# NTC.net
KiCad netlist of a schematic drawn in Altium Designer
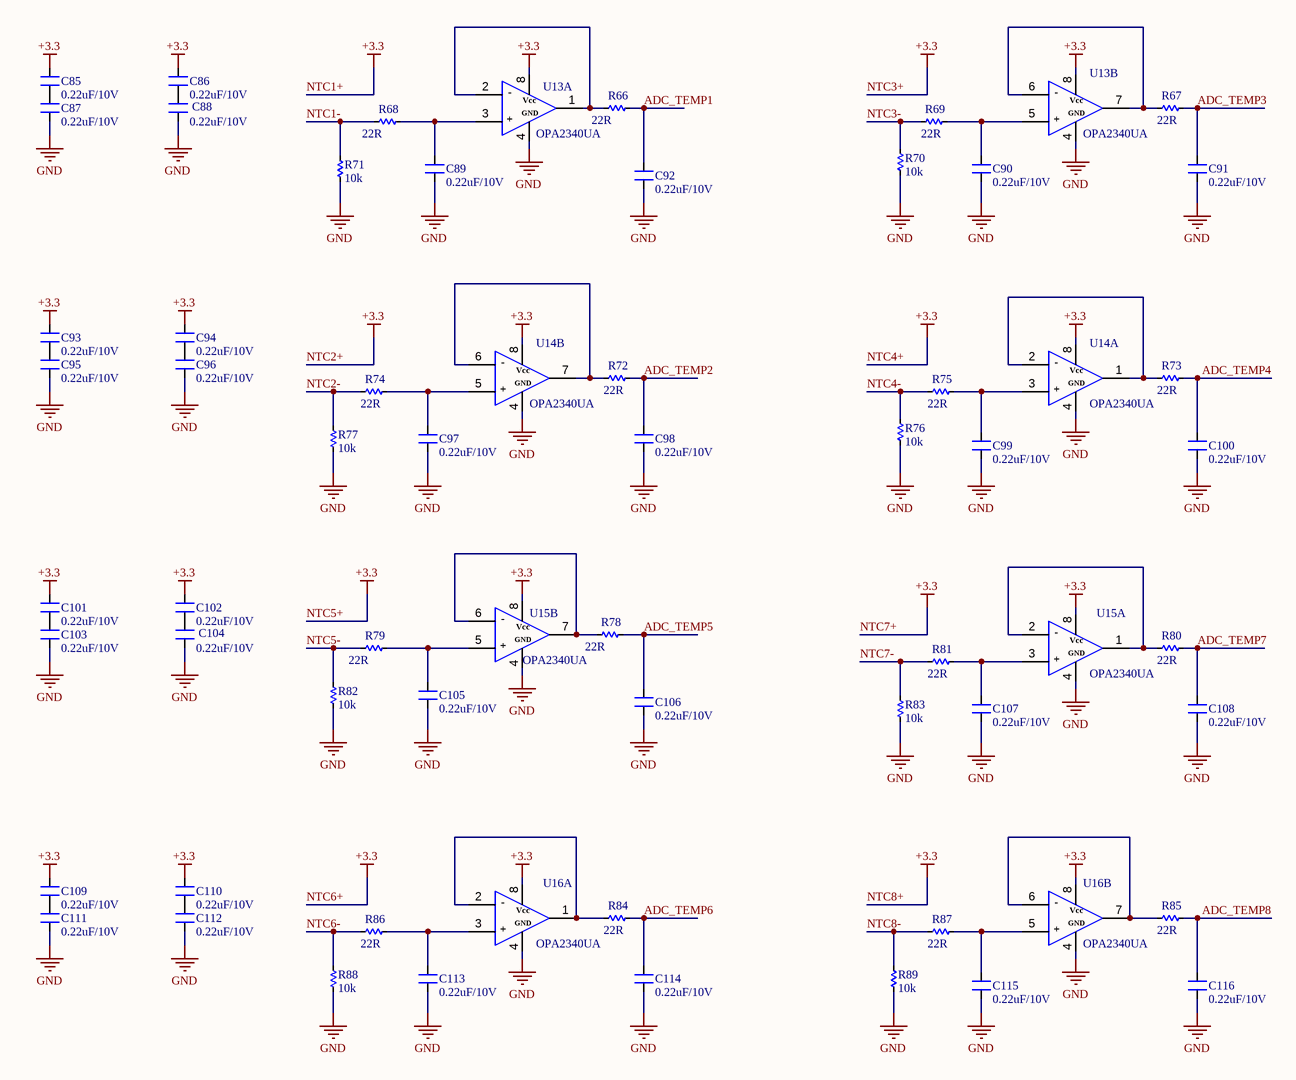
[diagram p0: NTC.SchDoc]

(export (version "E")
  (design (tool "Eeschema 10.0.6"))
  (components
    (comp (ref "C85")
      (value "0.22uF/10V")
      (footprint "CAP_C_1608X80")
      (libsource (lib "Sang_library") (part "Capacitors"))
    )
    (comp (ref "C86")
      (value "0.22uF/10V")
      (footprint "CAP_C_1608X80")
      (libsource (lib "Sang_library") (part "Capacitors"))
    )
    (comp (ref "C87")
      (value "0.22uF/10V")
      (footprint "CAP_C_1608X80")
      (libsource (lib "Sang_library") (part "Capacitors"))
    )
    (comp (ref "C88")
      (value "0.22uF/10V")
      (footprint "CAP_C_1608X80")
      (libsource (lib "Sang_library") (part "Capacitors"))
    )
    (comp (ref "C89")
      (value "0.22uF/10V")
      (footprint "CAP_C_1608X80")
      (libsource (lib "Sang_library") (part "Capacitors"))
    )
    (comp (ref "C90")
      (value "0.22uF/10V")
      (footprint "CAP_C_1608X80")
      (libsource (lib "Sang_library") (part "Capacitors"))
    )
    (comp (ref "C91")
      (value "0.22uF/10V")
      (footprint "CAP_C_1608X80")
      (libsource (lib "Sang_library") (part "Capacitors"))
    )
    (comp (ref "C92")
      (value "0.22uF/10V")
      (footprint "CAP_C_1608X80")
      (libsource (lib "Sang_library") (part "Capacitors"))
    )
    (comp (ref "C93")
      (value "0.22uF/10V")
      (footprint "CAP_C_1608X80")
      (libsource (lib "Sang_library") (part "Capacitors"))
    )
    (comp (ref "C94")
      (value "0.22uF/10V")
      (footprint "CAP_C_1608X80")
      (libsource (lib "Sang_library") (part "Capacitors"))
    )
    (comp (ref "C95")
      (value "0.22uF/10V")
      (footprint "CAP_C_1608X80")
      (libsource (lib "Sang_library") (part "Capacitors"))
    )
    (comp (ref "C96")
      (value "0.22uF/10V")
      (footprint "CAP_C_1608X80")
      (libsource (lib "Sang_library") (part "Capacitors"))
    )
    (comp (ref "C97")
      (value "0.22uF/10V")
      (footprint "CAP_C_1608X80")
      (libsource (lib "Sang_library") (part "Capacitors"))
    )
    (comp (ref "C98")
      (value "0.22uF/10V")
      (footprint "CAP_C_1608X80")
      (libsource (lib "Sang_library") (part "Capacitors"))
    )
    (comp (ref "C99")
      (value "0.22uF/10V")
      (footprint "CAP_C_1608X80")
      (libsource (lib "Sang_library") (part "Capacitors"))
    )
    (comp (ref "C100")
      (value "0.22uF/10V")
      (footprint "CAP_C_1608X80")
      (libsource (lib "Sang_library") (part "Capacitors"))
    )
    (comp (ref "C101")
      (value "0.22uF/10V")
      (footprint "CAP_C_1608X80")
      (libsource (lib "Sang_library") (part "Capacitors"))
    )
    (comp (ref "C102")
      (value "0.22uF/10V")
      (footprint "CAP_C_1608X80")
      (libsource (lib "Sang_library") (part "Capacitors"))
    )
    (comp (ref "C103")
      (value "0.22uF/10V")
      (footprint "CAP_C_1608X80")
      (libsource (lib "Sang_library") (part "Capacitors"))
    )
    (comp (ref "C104")
      (value "0.22uF/10V")
      (footprint "CAP_C_1608X80")
      (libsource (lib "Sang_library") (part "Capacitors"))
    )
    (comp (ref "C105")
      (value "0.22uF/10V")
      (footprint "CAP_C_1608X80")
      (libsource (lib "Sang_library") (part "Capacitors"))
    )
    (comp (ref "C106")
      (value "0.22uF/10V")
      (footprint "CAP_C_1608X80")
      (libsource (lib "Sang_library") (part "Capacitors"))
    )
    (comp (ref "C107")
      (value "0.22uF/10V")
      (footprint "CAP_C_1608X80")
      (libsource (lib "Sang_library") (part "Capacitors"))
    )
    (comp (ref "C108")
      (value "0.22uF/10V")
      (footprint "CAP_C_1608X80")
      (libsource (lib "Sang_library") (part "Capacitors"))
    )
    (comp (ref "C109")
      (value "0.22uF/10V")
      (footprint "CAP_C_1608X80")
      (libsource (lib "Sang_library") (part "Capacitors"))
    )
    (comp (ref "C110")
      (value "0.22uF/10V")
      (footprint "CAP_C_1608X80")
      (libsource (lib "Sang_library") (part "Capacitors"))
    )
    (comp (ref "C111")
      (value "0.22uF/10V")
      (footprint "CAP_C_1608X80")
      (libsource (lib "Sang_library") (part "Capacitors"))
    )
    (comp (ref "C112")
      (value "0.22uF/10V")
      (footprint "CAP_C_1608X80")
      (libsource (lib "Sang_library") (part "Capacitors"))
    )
    (comp (ref "C113")
      (value "0.22uF/10V")
      (footprint "CAP_C_1608X80")
      (libsource (lib "Sang_library") (part "Capacitors"))
    )
    (comp (ref "C114")
      (value "0.22uF/10V")
      (footprint "CAP_C_1608X80")
      (libsource (lib "Sang_library") (part "Capacitors"))
    )
    (comp (ref "C115")
      (value "0.22uF/10V")
      (footprint "CAP_C_1608X80")
      (libsource (lib "Sang_library") (part "Capacitors"))
    )
    (comp (ref "C116")
      (value "0.22uF/10V")
      (footprint "CAP_C_1608X80")
      (libsource (lib "Sang_library") (part "Capacitors"))
    )
    (comp (ref "R66")
      (value "22R")
      (footprint "RES_C_1608X60")
      (description "SMD")
      (fields
        (field (name "MANUFACTURER") "Generic Components")
        (field (name "PUBLISHER") "Altium Hobart Technology Centre")
      )
      (libsource (lib "Sang_library") (part "Res SMD"))
    )
    (comp (ref "R67")
      (value "22R")
      (footprint "RES_C_1608X60")
      (description "SMD")
      (fields
        (field (name "MANUFACTURER") "Generic Components")
        (field (name "PUBLISHER") "Altium Hobart Technology Centre")
      )
      (libsource (lib "Sang_library") (part "Res SMD"))
    )
    (comp (ref "R68")
      (value "22R")
      (footprint "RES_C_1608X60")
      (description "SMD")
      (fields
        (field (name "MANUFACTURER") "Generic Components")
        (field (name "PUBLISHER") "Altium Hobart Technology Centre")
      )
      (libsource (lib "Sang_library") (part "Res SMD"))
    )
    (comp (ref "R69")
      (value "22R")
      (footprint "RES_C_1608X60")
      (description "SMD")
      (fields
        (field (name "MANUFACTURER") "Generic Components")
        (field (name "PUBLISHER") "Altium Hobart Technology Centre")
      )
      (libsource (lib "Sang_library") (part "Res SMD"))
    )
    (comp (ref "R70")
      (value "10k")
      (footprint "RES_C_1608X60")
      (description "SMD")
      (fields
        (field (name "MANUFACTURER") "Generic Components")
        (field (name "PUBLISHER") "Altium Hobart Technology Centre")
      )
      (libsource (lib "Sang_library") (part "Res SMD"))
    )
    (comp (ref "R71")
      (value "10k")
      (footprint "RES_C_1608X60")
      (description "SMD")
      (fields
        (field (name "MANUFACTURER") "Generic Components")
        (field (name "PUBLISHER") "Altium Hobart Technology Centre")
      )
      (libsource (lib "Sang_library") (part "Res SMD"))
    )
    (comp (ref "R72")
      (value "22R")
      (footprint "RES_C_1608X60")
      (description "SMD")
      (fields
        (field (name "MANUFACTURER") "Generic Components")
        (field (name "PUBLISHER") "Altium Hobart Technology Centre")
      )
      (libsource (lib "Sang_library") (part "Res SMD"))
    )
    (comp (ref "R73")
      (value "22R")
      (footprint "RES_C_1608X60")
      (description "SMD")
      (fields
        (field (name "MANUFACTURER") "Generic Components")
        (field (name "PUBLISHER") "Altium Hobart Technology Centre")
      )
      (libsource (lib "Sang_library") (part "Res SMD"))
    )
    (comp (ref "R74")
      (value "22R")
      (footprint "RES_C_1608X60")
      (description "SMD")
      (fields
        (field (name "MANUFACTURER") "Generic Components")
        (field (name "PUBLISHER") "Altium Hobart Technology Centre")
      )
      (libsource (lib "Sang_library") (part "Res SMD"))
    )
    (comp (ref "R75")
      (value "22R")
      (footprint "RES_C_1608X60")
      (description "SMD")
      (fields
        (field (name "MANUFACTURER") "Generic Components")
        (field (name "PUBLISHER") "Altium Hobart Technology Centre")
      )
      (libsource (lib "Sang_library") (part "Res SMD"))
    )
    (comp (ref "R76")
      (value "10k")
      (footprint "RES_C_1608X60")
      (description "SMD")
      (fields
        (field (name "MANUFACTURER") "Generic Components")
        (field (name "PUBLISHER") "Altium Hobart Technology Centre")
      )
      (libsource (lib "Sang_library") (part "Res SMD"))
    )
    (comp (ref "R77")
      (value "10k")
      (footprint "RES_C_1608X60")
      (description "SMD")
      (fields
        (field (name "MANUFACTURER") "Generic Components")
        (field (name "PUBLISHER") "Altium Hobart Technology Centre")
      )
      (libsource (lib "Sang_library") (part "Res SMD"))
    )
    (comp (ref "R78")
      (value "22R")
      (footprint "RES_C_1608X60")
      (description "SMD")
      (fields
        (field (name "MANUFACTURER") "Generic Components")
        (field (name "PUBLISHER") "Altium Hobart Technology Centre")
      )
      (libsource (lib "Sang_library") (part "Res SMD"))
    )
    (comp (ref "R79")
      (value "22R")
      (footprint "RES_C_1608X60")
      (description "SMD")
      (fields
        (field (name "MANUFACTURER") "Generic Components")
        (field (name "PUBLISHER") "Altium Hobart Technology Centre")
      )
      (libsource (lib "Sang_library") (part "Res SMD"))
    )
    (comp (ref "R80")
      (value "22R")
      (footprint "RES_C_1608X60")
      (description "SMD")
      (fields
        (field (name "MANUFACTURER") "Generic Components")
        (field (name "PUBLISHER") "Altium Hobart Technology Centre")
      )
      (libsource (lib "Sang_library") (part "Res SMD"))
    )
    (comp (ref "R81")
      (value "22R")
      (footprint "RES_C_1608X60")
      (description "SMD")
      (fields
        (field (name "MANUFACTURER") "Generic Components")
        (field (name "PUBLISHER") "Altium Hobart Technology Centre")
      )
      (libsource (lib "Sang_library") (part "Res SMD"))
    )
    (comp (ref "R82")
      (value "10k")
      (footprint "RES_C_1608X60")
      (description "SMD")
      (fields
        (field (name "MANUFACTURER") "Generic Components")
        (field (name "PUBLISHER") "Altium Hobart Technology Centre")
      )
      (libsource (lib "Sang_library") (part "Res SMD"))
    )
    (comp (ref "R83")
      (value "10k")
      (footprint "RES_C_1608X60")
      (description "SMD")
      (fields
        (field (name "MANUFACTURER") "Generic Components")
        (field (name "PUBLISHER") "Altium Hobart Technology Centre")
      )
      (libsource (lib "Sang_library") (part "Res SMD"))
    )
    (comp (ref "R84")
      (value "22R")
      (footprint "RES_C_1608X60")
      (description "SMD")
      (fields
        (field (name "MANUFACTURER") "Generic Components")
        (field (name "PUBLISHER") "Altium Hobart Technology Centre")
      )
      (libsource (lib "Sang_library") (part "Res SMD"))
    )
    (comp (ref "R85")
      (value "22R")
      (footprint "RES_C_1608X60")
      (description "SMD")
      (fields
        (field (name "MANUFACTURER") "Generic Components")
        (field (name "PUBLISHER") "Altium Hobart Technology Centre")
      )
      (libsource (lib "Sang_library") (part "Res SMD"))
    )
    (comp (ref "R86")
      (value "22R")
      (footprint "RES_C_1608X60")
      (description "SMD")
      (fields
        (field (name "MANUFACTURER") "Generic Components")
        (field (name "PUBLISHER") "Altium Hobart Technology Centre")
      )
      (libsource (lib "Sang_library") (part "Res SMD"))
    )
    (comp (ref "R87")
      (value "22R")
      (footprint "RES_C_1608X60")
      (description "SMD")
      (fields
        (field (name "MANUFACTURER") "Generic Components")
        (field (name "PUBLISHER") "Altium Hobart Technology Centre")
      )
      (libsource (lib "Sang_library") (part "Res SMD"))
    )
    (comp (ref "R88")
      (value "10k")
      (footprint "RES_C_1608X60")
      (description "SMD")
      (fields
        (field (name "MANUFACTURER") "Generic Components")
        (field (name "PUBLISHER") "Altium Hobart Technology Centre")
      )
      (libsource (lib "Sang_library") (part "Res SMD"))
    )
    (comp (ref "R89")
      (value "10k")
      (footprint "RES_C_1608X60")
      (description "SMD")
      (fields
        (field (name "MANUFACTURER") "Generic Components")
        (field (name "PUBLISHER") "Altium Hobart Technology Centre")
      )
      (libsource (lib "Sang_library") (part "Res SMD"))
    )
    (comp (ref "U13")
      (value "OPA2340UA")
      (footprint "SO8")
      (libsource (lib "Sang_library") (part "OPA2340UA/2K5"))
    )
    (comp (ref "U14")
      (value "OPA2340UA")
      (footprint "SO8")
      (libsource (lib "Sang_library") (part "OPA2340UA/2K5"))
    )
    (comp (ref "U15")
      (value "OPA2340UA")
      (footprint "SO8")
      (libsource (lib "Sang_library") (part "OPA2340UA/2K5"))
    )
    (comp (ref "U16")
      (value "OPA2340UA")
      (footprint "SO8")
      (libsource (lib "Sang_library") (part "OPA2340UA/2K5"))
    )
  )
  (nets
    (net (code "1") (name "+3.3") (class "Default")
      (node (ref "C101") (pin "2") (pinfunction "2_2") (pintype "passive"))
      (node (ref "C102") (pin "2") (pinfunction "2_2") (pintype "passive"))
      (node (ref "C109") (pin "2") (pinfunction "2_2") (pintype "passive"))
      (node (ref "C110") (pin "2") (pinfunction "2_2") (pintype "passive"))
      (node (ref "C85") (pin "2") (pinfunction "2_2") (pintype "passive"))
      (node (ref "C86") (pin "2") (pinfunction "2_2") (pintype "passive"))
      (node (ref "C93") (pin "2") (pinfunction "2_2") (pintype "passive"))
      (node (ref "C94") (pin "2") (pinfunction "2_2") (pintype "passive"))
      (node (ref "U13") (pin "8") (pinfunction "8_8") (pintype "passive"))
      (node (ref "U14") (pin "8") (pinfunction "8_8") (pintype "passive"))
      (node (ref "U15") (pin "8") (pinfunction "8_8") (pintype "passive"))
      (node (ref "U16") (pin "8") (pinfunction "8_8") (pintype "passive"))
    )
    (net (code "2") (name "/ADC_TEMP1") (class "Default")
      (node (ref "C92") (pin "2") (pinfunction "2_2") (pintype "passive"))
      (node (ref "R66") (pin "2") (pinfunction "2_2") (pintype "passive"))
    )
    (net (code "3") (name "/ADC_TEMP2") (class "Default")
      (node (ref "C98") (pin "2") (pinfunction "2_2") (pintype "passive"))
      (node (ref "R72") (pin "2") (pinfunction "2_2") (pintype "passive"))
    )
    (net (code "4") (name "/ADC_TEMP3") (class "Default")
      (node (ref "C91") (pin "2") (pinfunction "2_2") (pintype "passive"))
      (node (ref "R67") (pin "2") (pinfunction "2_2") (pintype "passive"))
    )
    (net (code "5") (name "/ADC_TEMP4") (class "Default")
      (node (ref "C100") (pin "2") (pinfunction "2_2") (pintype "passive"))
      (node (ref "R73") (pin "2") (pinfunction "2_2") (pintype "passive"))
    )
    (net (code "6") (name "/ADC_TEMP5") (class "Default")
      (node (ref "C106") (pin "2") (pinfunction "2_2") (pintype "passive"))
      (node (ref "R78") (pin "2") (pinfunction "2_2") (pintype "passive"))
    )
    (net (code "7") (name "/ADC_TEMP6") (class "Default")
      (node (ref "C114") (pin "2") (pinfunction "2_2") (pintype "passive"))
      (node (ref "R84") (pin "2") (pinfunction "2_2") (pintype "passive"))
    )
    (net (code "8") (name "/ADC_TEMP7") (class "Default")
      (node (ref "C108") (pin "2") (pinfunction "2_2") (pintype "passive"))
      (node (ref "R80") (pin "2") (pinfunction "2_2") (pintype "passive"))
    )
    (net (code "9") (name "/ADC_TEMP8") (class "Default")
      (node (ref "C116") (pin "2") (pinfunction "2_2") (pintype "passive"))
      (node (ref "R85") (pin "2") (pinfunction "2_2") (pintype "passive"))
    )
    (net (code "10") (name "/NTC1-") (class "Default")
      (node (ref "R68") (pin "1") (pinfunction "1_1") (pintype "passive"))
      (node (ref "R71") (pin "1") (pinfunction "1_1") (pintype "passive"))
    )
    (net (code "11") (name "/NTC2-") (class "Default")
      (node (ref "R74") (pin "1") (pinfunction "1_1") (pintype "passive"))
      (node (ref "R77") (pin "1") (pinfunction "1_1") (pintype "passive"))
    )
    (net (code "12") (name "/NTC3-") (class "Default")
      (node (ref "R69") (pin "1") (pinfunction "1_1") (pintype "passive"))
      (node (ref "R70") (pin "1") (pinfunction "1_1") (pintype "passive"))
    )
    (net (code "13") (name "/NTC4-") (class "Default")
      (node (ref "R75") (pin "1") (pinfunction "1_1") (pintype "passive"))
      (node (ref "R76") (pin "1") (pinfunction "1_1") (pintype "passive"))
    )
    (net (code "14") (name "/NTC5-") (class "Default")
      (node (ref "R79") (pin "1") (pinfunction "1_1") (pintype "passive"))
      (node (ref "R82") (pin "1") (pinfunction "1_1") (pintype "passive"))
    )
    (net (code "15") (name "/NTC6-") (class "Default")
      (node (ref "R86") (pin "1") (pinfunction "1_1") (pintype "passive"))
      (node (ref "R88") (pin "1") (pinfunction "1_1") (pintype "passive"))
    )
    (net (code "16") (name "/NTC7-") (class "Default")
      (node (ref "R81") (pin "1") (pinfunction "1_1") (pintype "passive"))
      (node (ref "R83") (pin "1") (pinfunction "1_1") (pintype "passive"))
    )
    (net (code "17") (name "/NTC8-") (class "Default")
      (node (ref "R87") (pin "1") (pinfunction "1_1") (pintype "passive"))
      (node (ref "R89") (pin "1") (pinfunction "1_1") (pintype "passive"))
    )
    (net (code "18") (name "GND") (class "Default")
      (node (ref "C100") (pin "1") (pinfunction "1_1") (pintype "passive"))
      (node (ref "C103") (pin "1") (pinfunction "1_1") (pintype "passive"))
      (node (ref "C104") (pin "1") (pinfunction "1_1") (pintype "passive"))
      (node (ref "C105") (pin "1") (pinfunction "1_1") (pintype "passive"))
      (node (ref "C106") (pin "1") (pinfunction "1_1") (pintype "passive"))
      (node (ref "C107") (pin "1") (pinfunction "1_1") (pintype "passive"))
      (node (ref "C108") (pin "1") (pinfunction "1_1") (pintype "passive"))
      (node (ref "C111") (pin "1") (pinfunction "1_1") (pintype "passive"))
      (node (ref "C112") (pin "1") (pinfunction "1_1") (pintype "passive"))
      (node (ref "C113") (pin "1") (pinfunction "1_1") (pintype "passive"))
      (node (ref "C114") (pin "1") (pinfunction "1_1") (pintype "passive"))
      (node (ref "C115") (pin "1") (pinfunction "1_1") (pintype "passive"))
      (node (ref "C116") (pin "1") (pinfunction "1_1") (pintype "passive"))
      (node (ref "C87") (pin "1") (pinfunction "1_1") (pintype "passive"))
      (node (ref "C88") (pin "1") (pinfunction "1_1") (pintype "passive"))
      (node (ref "C89") (pin "1") (pinfunction "1_1") (pintype "passive"))
      (node (ref "C90") (pin "1") (pinfunction "1_1") (pintype "passive"))
      (node (ref "C91") (pin "1") (pinfunction "1_1") (pintype "passive"))
      (node (ref "C92") (pin "1") (pinfunction "1_1") (pintype "passive"))
      (node (ref "C95") (pin "1") (pinfunction "1_1") (pintype "passive"))
      (node (ref "C96") (pin "1") (pinfunction "1_1") (pintype "passive"))
      (node (ref "C97") (pin "1") (pinfunction "1_1") (pintype "passive"))
      (node (ref "C98") (pin "1") (pinfunction "1_1") (pintype "passive"))
      (node (ref "C99") (pin "1") (pinfunction "1_1") (pintype "passive"))
      (node (ref "R70") (pin "2") (pinfunction "2_2") (pintype "passive"))
      (node (ref "R71") (pin "2") (pinfunction "2_2") (pintype "passive"))
      (node (ref "R76") (pin "2") (pinfunction "2_2") (pintype "passive"))
      (node (ref "R77") (pin "2") (pinfunction "2_2") (pintype "passive"))
      (node (ref "R82") (pin "2") (pinfunction "2_2") (pintype "passive"))
      (node (ref "R83") (pin "2") (pinfunction "2_2") (pintype "passive"))
      (node (ref "R88") (pin "2") (pinfunction "2_2") (pintype "passive"))
      (node (ref "R89") (pin "2") (pinfunction "2_2") (pintype "passive"))
      (node (ref "U13") (pin "4") (pinfunction "4_4") (pintype "passive"))
      (node (ref "U14") (pin "4") (pinfunction "4_4") (pintype "passive"))
      (node (ref "U15") (pin "4") (pinfunction "4_4") (pintype "passive"))
      (node (ref "U16") (pin "4") (pinfunction "4_4") (pintype "passive"))
    )
    (net (code "19") (name "Net-(C85-Pad1)") (class "Default")
      (node (ref "C85") (pin "1") (pinfunction "1_1") (pintype "passive"))
      (node (ref "C87") (pin "2") (pinfunction "2_2") (pintype "passive"))
    )
    (net (code "20") (name "Net-(C86-Pad1)") (class "Default")
      (node (ref "C86") (pin "1") (pinfunction "1_1") (pintype "passive"))
      (node (ref "C88") (pin "2") (pinfunction "2_2") (pintype "passive"))
    )
    (net (code "21") (name "Net-(C89-Pad2)") (class "Default")
      (node (ref "C89") (pin "2") (pinfunction "2_2") (pintype "passive"))
      (node (ref "R68") (pin "2") (pinfunction "2_2") (pintype "passive"))
      (node (ref "U13") (pin "3") (pinfunction "3_3") (pintype "passive"))
    )
    (net (code "22") (name "Net-(C90-Pad2)") (class "Default")
      (node (ref "C90") (pin "2") (pinfunction "2_2") (pintype "passive"))
      (node (ref "R69") (pin "2") (pinfunction "2_2") (pintype "passive"))
      (node (ref "U13") (pin "5") (pinfunction "5_5") (pintype "passive"))
    )
    (net (code "23") (name "Net-(C93-Pad1)") (class "Default")
      (node (ref "C93") (pin "1") (pinfunction "1_1") (pintype "passive"))
      (node (ref "C95") (pin "2") (pinfunction "2_2") (pintype "passive"))
    )
    (net (code "24") (name "Net-(C94-Pad1)") (class "Default")
      (node (ref "C94") (pin "1") (pinfunction "1_1") (pintype "passive"))
      (node (ref "C96") (pin "2") (pinfunction "2_2") (pintype "passive"))
    )
    (net (code "25") (name "Net-(C97-Pad2)") (class "Default")
      (node (ref "C97") (pin "2") (pinfunction "2_2") (pintype "passive"))
      (node (ref "R74") (pin "2") (pinfunction "2_2") (pintype "passive"))
      (node (ref "U14") (pin "5") (pinfunction "5_5") (pintype "passive"))
    )
    (net (code "26") (name "Net-(C99-Pad2)") (class "Default")
      (node (ref "C99") (pin "2") (pinfunction "2_2") (pintype "passive"))
      (node (ref "R75") (pin "2") (pinfunction "2_2") (pintype "passive"))
      (node (ref "U14") (pin "3") (pinfunction "3_3") (pintype "passive"))
    )
    (net (code "27") (name "Net-(C101-Pad1)") (class "Default")
      (node (ref "C101") (pin "1") (pinfunction "1_1") (pintype "passive"))
      (node (ref "C103") (pin "2") (pinfunction "2_2") (pintype "passive"))
    )
    (net (code "28") (name "Net-(C102-Pad1)") (class "Default")
      (node (ref "C102") (pin "1") (pinfunction "1_1") (pintype "passive"))
      (node (ref "C104") (pin "2") (pinfunction "2_2") (pintype "passive"))
    )
    (net (code "29") (name "Net-(C105-Pad2)") (class "Default")
      (node (ref "C105") (pin "2") (pinfunction "2_2") (pintype "passive"))
      (node (ref "R79") (pin "2") (pinfunction "2_2") (pintype "passive"))
      (node (ref "U15") (pin "5") (pinfunction "5_5") (pintype "passive"))
    )
    (net (code "30") (name "Net-(C107-Pad2)") (class "Default")
      (node (ref "C107") (pin "2") (pinfunction "2_2") (pintype "passive"))
      (node (ref "R81") (pin "2") (pinfunction "2_2") (pintype "passive"))
      (node (ref "U15") (pin "3") (pinfunction "3_3") (pintype "passive"))
    )
    (net (code "31") (name "Net-(C109-Pad1)") (class "Default")
      (node (ref "C109") (pin "1") (pinfunction "1_1") (pintype "passive"))
      (node (ref "C111") (pin "2") (pinfunction "2_2") (pintype "passive"))
    )
    (net (code "32") (name "Net-(C110-Pad1)") (class "Default")
      (node (ref "C110") (pin "1") (pinfunction "1_1") (pintype "passive"))
      (node (ref "C112") (pin "2") (pinfunction "2_2") (pintype "passive"))
    )
    (net (code "33") (name "Net-(C113-Pad2)") (class "Default")
      (node (ref "C113") (pin "2") (pinfunction "2_2") (pintype "passive"))
      (node (ref "R86") (pin "2") (pinfunction "2_2") (pintype "passive"))
      (node (ref "U16") (pin "3") (pinfunction "3_3") (pintype "passive"))
    )
    (net (code "34") (name "Net-(C115-Pad2)") (class "Default")
      (node (ref "C115") (pin "2") (pinfunction "2_2") (pintype "passive"))
      (node (ref "R87") (pin "2") (pinfunction "2_2") (pintype "passive"))
      (node (ref "U16") (pin "5") (pinfunction "5_5") (pintype "passive"))
    )
    (net (code "35") (name "Net-(R66-Pad1)") (class "Default")
      (node (ref "R66") (pin "1") (pinfunction "1_1") (pintype "passive"))
      (node (ref "U13") (pin "1") (pinfunction "1_1") (pintype "passive"))
      (node (ref "U13") (pin "2") (pinfunction "2_2") (pintype "passive"))
    )
    (net (code "36") (name "Net-(R67-Pad1)") (class "Default")
      (node (ref "R67") (pin "1") (pinfunction "1_1") (pintype "passive"))
      (node (ref "U13") (pin "6") (pinfunction "6_6") (pintype "passive"))
      (node (ref "U13") (pin "7") (pinfunction "7_7") (pintype "passive"))
    )
    (net (code "37") (name "Net-(R72-Pad1)") (class "Default")
      (node (ref "R72") (pin "1") (pinfunction "1_1") (pintype "passive"))
      (node (ref "U14") (pin "6") (pinfunction "6_6") (pintype "passive"))
      (node (ref "U14") (pin "7") (pinfunction "7_7") (pintype "passive"))
    )
    (net (code "38") (name "Net-(R73-Pad1)") (class "Default")
      (node (ref "R73") (pin "1") (pinfunction "1_1") (pintype "passive"))
      (node (ref "U14") (pin "1") (pinfunction "1_1") (pintype "passive"))
      (node (ref "U14") (pin "2") (pinfunction "2_2") (pintype "passive"))
    )
    (net (code "39") (name "Net-(R78-Pad1)") (class "Default")
      (node (ref "R78") (pin "1") (pinfunction "1_1") (pintype "passive"))
      (node (ref "U15") (pin "6") (pinfunction "6_6") (pintype "passive"))
      (node (ref "U15") (pin "7") (pinfunction "7_7") (pintype "passive"))
    )
    (net (code "40") (name "Net-(R80-Pad1)") (class "Default")
      (node (ref "R80") (pin "1") (pinfunction "1_1") (pintype "passive"))
      (node (ref "U15") (pin "1") (pinfunction "1_1") (pintype "passive"))
      (node (ref "U15") (pin "2") (pinfunction "2_2") (pintype "passive"))
    )
    (net (code "41") (name "Net-(R84-Pad1)") (class "Default")
      (node (ref "R84") (pin "1") (pinfunction "1_1") (pintype "passive"))
      (node (ref "U16") (pin "1") (pinfunction "1_1") (pintype "passive"))
      (node (ref "U16") (pin "2") (pinfunction "2_2") (pintype "passive"))
    )
    (net (code "42") (name "Net-(R85-Pad1)") (class "Default")
      (node (ref "R85") (pin "1") (pinfunction "1_1") (pintype "passive"))
      (node (ref "U16") (pin "6") (pinfunction "6_6") (pintype "passive"))
      (node (ref "U16") (pin "7") (pinfunction "7_7") (pintype "passive"))
    )
  )
)
